# Sheet1.net
KiCad netlist of a schematic drawn in Altium Designer
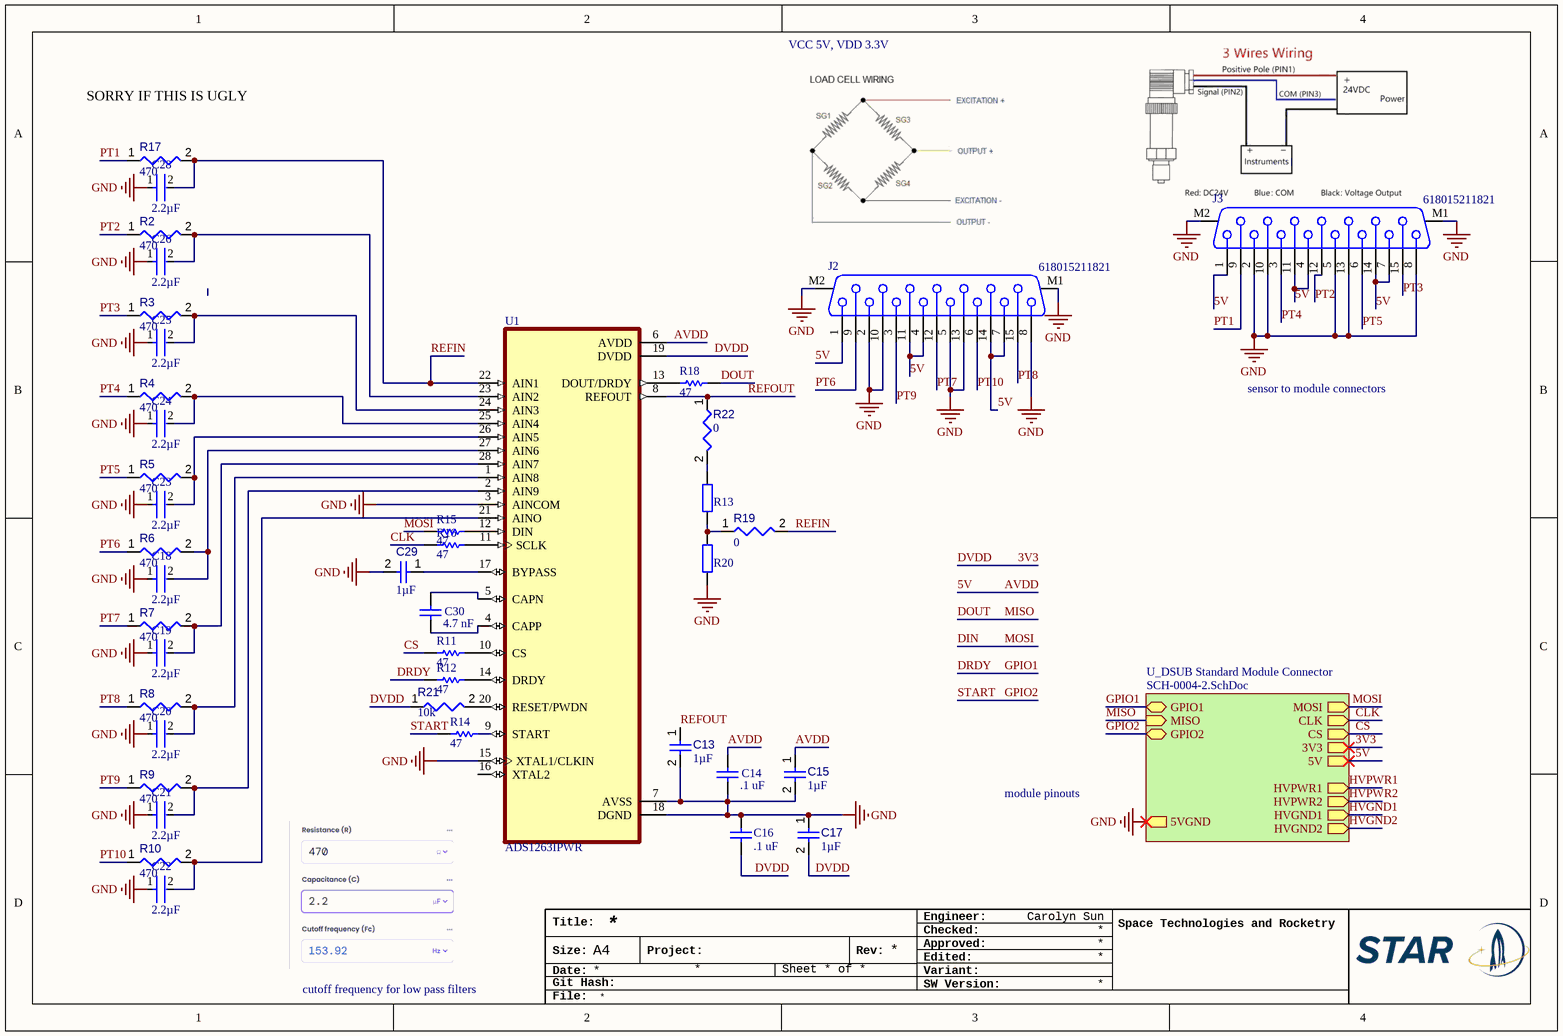
[diagram p0: Sheet1.SchDoc]

(export (version "E")
  (design (tool "Eeschema 10.0.6"))
  (components
    (comp (ref "C13")
      (value "1µF")
      (footprint "CAPC1608X94X35NL15T15")
      (description "Chip Capacitor, 1 uF, +/- 10%, 16 V, 0603 (1608 Metric)")
      (fields (field (name "TOLERANCE") "10%") (field (name "Comment") "Capacitor 1 uF +/- 10% 16 V 0603"))
      (libsource (lib "UCBerkeleySTAR") (part "CAP-NP-2"))
    )
    (comp (ref "C14")
      (value ".1 uF")
      (footprint "CAPC1608X90X35ML10T15")
      (description "Chip Capacitor, 0.1 uF, +/- 10%, 50 V, -55 to 125 degC, 0603 (1608 Metric), RoHS, Tape and Reel")
      (fields (field (name "TOLERANCE") "10%") (field (name "VOLTAGE") "50V"))
      (libsource (lib "Altium Content Vault") (part "CAP-NP-2"))
    )
    (comp (ref "C15")
      (value "1µF")
      (footprint "CAPC1608X94X35NL15T15")
      (description "Chip Capacitor, 1 uF, +/- 10%, 16 V, 0603 (1608 Metric)")
      (fields (field (name "TOLERANCE") "10%") (field (name "Comment") "Capacitor 1 uF +/- 10% 16 V 0603"))
      (libsource (lib "UCBerkeleySTAR") (part "CAP-NP-2"))
    )
    (comp (ref "C16")
      (value ".1 uF")
      (footprint "CAPC1608X90X35ML10T15")
      (description "Chip Capacitor, 0.1 uF, +/- 10%, 50 V, -55 to 125 degC, 0603 (1608 Metric), RoHS, Tape and Reel")
      (fields (field (name "TOLERANCE") "10%") (field (name "VOLTAGE") "50V"))
      (libsource (lib "Altium Content Vault") (part "CAP-NP-2"))
    )
    (comp (ref "C17")
      (value "1µF")
      (footprint "CAPC1608X94X35NL15T15")
      (description "Chip Capacitor, 1 uF, +/- 10%, 16 V, 0603 (1608 Metric)")
      (fields (field (name "TOLERANCE") "10%") (field (name "Comment") "Capacitor 1 uF +/- 10% 16 V 0603"))
      (libsource (lib "UCBerkeleySTAR") (part "CAP-NP-2"))
    )
    (comp (ref "C18")
      (value "2.2µF")
      (footprint "FP-CL21-IPC_B")
      (fields (field (name "Comment") "CL21B225KPFNNNE"))
      (libsource (lib "UCBerkeleySTAR") (part "b4654b650e69147ec39a6b967a45e02"))
    )
    (comp (ref "C19")
      (value "2.2µF")
      (footprint "FP-CL21-IPC_B")
      (fields (field (name "Comment") "CL21B225KPFNNNE"))
      (libsource (lib "UCBerkeleySTAR") (part "b4654b650e69147ec39a6b967a45e02"))
    )
    (comp (ref "C20")
      (value "2.2µF")
      (footprint "FP-CL21-IPC_B")
      (fields (field (name "Comment") "CL21B225KPFNNNE"))
      (libsource (lib "UCBerkeleySTAR") (part "b4654b650e69147ec39a6b967a45e02"))
    )
    (comp (ref "C21")
      (value "2.2µF")
      (footprint "FP-CL21-IPC_B")
      (fields (field (name "Comment") "CL21B225KPFNNNE"))
      (libsource (lib "UCBerkeleySTAR") (part "b4654b650e69147ec39a6b967a45e02"))
    )
    (comp (ref "C22")
      (value "2.2µF")
      (footprint "FP-CL21-IPC_B")
      (fields (field (name "Comment") "CL21B225KPFNNNE"))
      (libsource (lib "UCBerkeleySTAR") (part "b4654b650e69147ec39a6b967a45e02"))
    )
    (comp (ref "C23")
      (value "2.2µF")
      (footprint "FP-CL21-IPC_B")
      (fields (field (name "Comment") "CL21B225KPFNNNE"))
      (libsource (lib "UCBerkeleySTAR") (part "b4654b650e69147ec39a6b967a45e02"))
    )
    (comp (ref "C24")
      (value "2.2µF")
      (footprint "FP-CL21-IPC_B")
      (fields (field (name "Comment") "CL21B225KPFNNNE"))
      (libsource (lib "UCBerkeleySTAR") (part "b4654b650e69147ec39a6b967a45e02"))
    )
    (comp (ref "C25")
      (value "2.2µF")
      (footprint "FP-CL21-IPC_B")
      (fields (field (name "Comment") "CL21B225KPFNNNE"))
      (libsource (lib "UCBerkeleySTAR") (part "b4654b650e69147ec39a6b967a45e02"))
    )
    (comp (ref "C26")
      (value "2.2µF")
      (footprint "FP-CL21-IPC_B")
      (fields (field (name "Comment") "CL21B225KPFNNNE"))
      (libsource (lib "UCBerkeleySTAR") (part "b4654b650e69147ec39a6b967a45e02"))
    )
    (comp (ref "C28")
      (value "2.2µF")
      (footprint "FP-CL21-IPC_B")
      (fields (field (name "Comment") "CL21B225KPFNNNE"))
      (libsource (lib "UCBerkeleySTAR") (part "b4654b650e69147ec39a6b967a45e02"))
    )
    (comp (ref "C29")
      (value "1µF")
      (footprint "CAPC1608X94X35NL15T15")
      (description "Chip Capacitor, 1 uF, +/- 10%, 16 V, 0603 (1608 Metric)")
      (fields (field (name "TOLERANCE") "10%") (field (name "Comment") "Capacitor 1 uF +/- 10% 16 V 0603"))
      (libsource (lib "UCBerkeleySTAR") (part "CAP-NP-2"))
    )
    (comp (ref "C30")
      (value "4.7 nF")
      (footprint "CAPC1608X90X35ML10T15")
      (fields (field (name "PART NUMBER") "GRM188R71H472KA01D") (field (name "MANUFACTURER") "Murata"))
      (libsource (lib "Altium Content Vault") (part "CAP"))
    )
    (comp (ref "J2")
      (value "618015211821")
      (footprint "618015211821")
      (description "D Type Connector, 15 Contact(s), Female, Solder Terminal, Locking, Plug")
      (libsource (lib "UCBerkeleySTAR") (part "D-Sub_Female_15p"))
    )
    (comp (ref "J3")
      (value "618015211821")
      (footprint "618015211821")
      (description "D Type Connector, 15 Contact(s), Female, Solder Terminal, Locking, Plug")
      (libsource (lib "UCBerkeleySTAR") (part "D-Sub_Female_15p"))
    )
    (comp (ref "R2")
      (value "470")
      (footprint "RESC0805(2012)_L")
      (description "470R 0.125W 5% 0805 (2012 Metric)  SMD")
      (fields (field (name "POWER") "125mW") (field (name "TOLERANCE") "5%"))
      (libsource (lib "UCBerkeleySTAR") (part "470R5J"))
    )
    (comp (ref "R3")
      (value "470")
      (footprint "RESC0805(2012)_L")
      (description "470R 0.125W 5% 0805 (2012 Metric)  SMD")
      (fields (field (name "POWER") "125mW") (field (name "TOLERANCE") "5%"))
      (libsource (lib "UCBerkeleySTAR") (part "470R5J"))
    )
    (comp (ref "R4")
      (value "470")
      (footprint "RESC0805(2012)_L")
      (description "470R 0.125W 5% 0805 (2012 Metric)  SMD")
      (fields (field (name "POWER") "125mW") (field (name "TOLERANCE") "5%"))
      (libsource (lib "UCBerkeleySTAR") (part "470R5J"))
    )
    (comp (ref "R5")
      (value "470")
      (footprint "RESC0805(2012)_L")
      (description "470R 0.125W 5% 0805 (2012 Metric)  SMD")
      (fields (field (name "POWER") "125mW") (field (name "TOLERANCE") "5%"))
      (libsource (lib "UCBerkeleySTAR") (part "470R5J"))
    )
    (comp (ref "R6")
      (value "470")
      (footprint "RESC0805(2012)_L")
      (description "470R 0.125W 5% 0805 (2012 Metric)  SMD")
      (fields (field (name "POWER") "125mW") (field (name "TOLERANCE") "5%"))
      (libsource (lib "UCBerkeleySTAR") (part "470R5J"))
    )
    (comp (ref "R7")
      (value "470")
      (footprint "RESC0805(2012)_L")
      (description "470R 0.125W 5% 0805 (2012 Metric)  SMD")
      (fields (field (name "POWER") "125mW") (field (name "TOLERANCE") "5%"))
      (libsource (lib "UCBerkeleySTAR") (part "470R5J"))
    )
    (comp (ref "R8")
      (value "470")
      (footprint "RESC0805(2012)_L")
      (description "470R 0.125W 5% 0805 (2012 Metric)  SMD")
      (fields (field (name "POWER") "125mW") (field (name "TOLERANCE") "5%"))
      (libsource (lib "UCBerkeleySTAR") (part "470R5J"))
    )
    (comp (ref "R9")
      (value "470")
      (footprint "RESC0805(2012)_L")
      (description "470R 0.125W 5% 0805 (2012 Metric)  SMD")
      (fields (field (name "POWER") "125mW") (field (name "TOLERANCE") "5%"))
      (libsource (lib "UCBerkeleySTAR") (part "470R5J"))
    )
    (comp (ref "R10")
      (value "470")
      (footprint "RESC0805(2012)_L")
      (description "470R 0.125W 5% 0805 (2012 Metric)  SMD")
      (fields (field (name "POWER") "125mW") (field (name "TOLERANCE") "5%"))
      (libsource (lib "UCBerkeleySTAR") (part "470R5J"))
    )
    (comp (ref "R11")
      (value "47")
      (footprint "RESC1609X50X30LL10T20")
      (fields (field (name "MANUFACTURER") "Vishay Dale") (field (name "PART NUMBER") "CRCW060347R0FKEA"))
      (libsource (lib "Altium Content Vault") (part "RES"))
    )
    (comp (ref "R12")
      (value "47")
      (footprint "RESC1609X50X30LL10T20")
      (fields (field (name "MANUFACTURER") "Vishay Dale") (field (name "PART NUMBER") "CRCW060347R0FKEA"))
      (libsource (lib "Altium Content Vault") (part "RES"))
    )
    (comp (ref "R13")
      (value "RES_0603")
      (footprint "RES_0603")
      (description "Resistor SMD 0603")
      (fields (field (name "SOURCE") "Schematic-Lib-PhilsLab.SchLib"))
      (libsource (lib "UCBerkeleySTAR") (part "RES_5931"))
    )
    (comp (ref "R14")
      (value "47")
      (footprint "RESC1609X50X30LL10T20")
      (fields (field (name "MANUFACTURER") "Vishay Dale") (field (name "PART NUMBER") "CRCW060347R0FKEA"))
      (libsource (lib "Altium Content Vault") (part "RES"))
    )
    (comp (ref "R15")
      (value "47")
      (footprint "RESC1609X50X30LL10T20")
      (fields (field (name "MANUFACTURER") "Vishay Dale") (field (name "PART NUMBER") "CRCW060347R0FKEA"))
      (libsource (lib "Altium Content Vault") (part "RES"))
    )
    (comp (ref "R16")
      (value "47")
      (footprint "RESC1609X50X30LL10T20")
      (fields (field (name "MANUFACTURER") "Vishay Dale") (field (name "PART NUMBER") "CRCW060347R0FKEA"))
      (libsource (lib "Altium Content Vault") (part "RES"))
    )
    (comp (ref "R17")
      (value "470")
      (footprint "RESC0805(2012)_L")
      (description "470R 0.125W 5% 0805 (2012 Metric)  SMD")
      (fields (field (name "POWER") "125mW") (field (name "TOLERANCE") "5%"))
      (libsource (lib "UCBerkeleySTAR") (part "470R5J"))
    )
    (comp (ref "R18")
      (value "47")
      (footprint "RESC1609X50X30LL10T20")
      (fields (field (name "MANUFACTURER") "Vishay Dale") (field (name "PART NUMBER") "CRCW060347R0FKEA"))
      (libsource (lib "Altium Content Vault") (part "RES"))
    )
    (comp (ref "R19")
      (value "0")
      (footprint "RESC0603(1608)_L")
      (description "Jumper 0603")
      (libsource (lib "UCBerkeleySTAR") (part "RES-2"))
    )
    (comp (ref "R20")
      (value "RES_0603")
      (footprint "RES_0603")
      (description "Resistor SMD 0603")
      (fields (field (name "SOURCE") "Schematic-Lib-PhilsLab.SchLib"))
      (libsource (lib "UCBerkeleySTAR") (part "RES_5931"))
    )
    (comp (ref "R21")
      (value "10k")
      (footprint "RESC1608X55X25ML10T15")
      (description "Chip Resistor, 10 KOhm, +/- 1%, 01 W, -55 to 155 degC, 0603 (1608 Metric)")
      (fields (field (name "POWER") "100mW") (field (name "TOLERANCE") "1%"))
      (libsource (lib "UCBerkeleySTAR") (part "RES-2"))
    )
    (comp (ref "R22")
      (value "0")
      (footprint "RESC0603(1608)_L")
      (description "Jumper 0603")
      (libsource (lib "UCBerkeleySTAR") (part "RES-2"))
    )
    (comp (ref "U1")
      (value "ADS1263IPWR")
      (footprint "SOP65P640X120-28N")
      (description "32-bit 38-kSPS 10-ch delta-sigma ADC with PGA, VREF and auxiliary ADC for factory automation")
      (fields (field (name "MF") "Texas Instruments"))
      (libsource (lib "UCBerkeleySTAR") (part "ADS1263IPWR"))
    )
  )
  (nets
    (net (code "1") (name "/3V3") (class "Default")
      (node (ref "C16") (pin "1") (pinfunction "1_1") (pintype "passive"))
      (node (ref "C17") (pin "2") (pinfunction "2_2") (pintype "passive"))
      (node (ref "R21") (pin "1") (pinfunction "1_1") (pintype "passive"))
      (node (ref "U1") (pin "19") (pinfunction "DVDD_19") (pintype "power_in"))
    )
    (net (code "2") (name "/5V") (class "Default")
      (node (ref "C14") (pin "2") (pinfunction "2_2") (pintype "passive"))
      (node (ref "C15") (pin "1") (pinfunction "1_1") (pintype "passive"))
      (node (ref "J2") (pin "1") (pinfunction "1_1") (pintype "passive"))
      (node (ref "J2") (pin "11") (pinfunction "11_11") (pintype "passive"))
      (node (ref "J2") (pin "14") (pinfunction "14_14") (pintype "passive"))
      (node (ref "J2") (pin "4") (pinfunction "4_4") (pintype "passive"))
      (node (ref "J2") (pin "7") (pinfunction "7_7") (pintype "passive"))
      (node (ref "J3") (pin "1") (pinfunction "1_1") (pintype "passive"))
      (node (ref "J3") (pin "11") (pinfunction "11_11") (pintype "passive"))
      (node (ref "J3") (pin "14") (pinfunction "14_14") (pintype "passive"))
      (node (ref "J3") (pin "4") (pinfunction "4_4") (pintype "passive"))
      (node (ref "J3") (pin "7") (pinfunction "7_7") (pintype "passive"))
      (node (ref "U1") (pin "6") (pinfunction "AVDD_6") (pintype "power_in"))
    )
    (net (code "3") (name "/CLK") (class "Default")
      (node (ref "R16") (pin "1") (pinfunction "1_1") (pintype "passive"))
    )
    (net (code "4") (name "/CS") (class "Default")
      (node (ref "R11") (pin "1") (pinfunction "1_1") (pintype "passive"))
    )
    (net (code "5") (name "/DIN") (class "Default")
      (node (ref "R15") (pin "1") (pinfunction "1_1") (pintype "passive"))
    )
    (net (code "6") (name "/DOUT") (class "Default")
      (node (ref "R18") (pin "2") (pinfunction "2_2") (pintype "passive"))
    )
    (net (code "7") (name "/DRDY") (class "Default")
      (node (ref "R12") (pin "1") (pinfunction "1_1") (pintype "passive"))
    )
    (net (code "8") (name "/GPIO2") (class "Default")
      (node (ref "R14") (pin "1") (pinfunction "1_1") (pintype "passive"))
    )
    (net (code "13") (name "/PT1") (class "Default")
      (node (ref "J3") (pin "9") (pinfunction "9_9") (pintype "passive"))
      (node (ref "R17") (pin "1") (pinfunction "1_1") (pintype "passive"))
    )
    (net (code "14") (name "/PT2") (class "Default")
      (node (ref "J3") (pin "12") (pinfunction "12_12") (pintype "passive"))
      (node (ref "R2") (pin "1") (pinfunction "1_1") (pintype "passive"))
    )
    (net (code "15") (name "/PT3") (class "Default")
      (node (ref "J3") (pin "15") (pinfunction "15_15") (pintype "passive"))
      (node (ref "R3") (pin "1") (pinfunction "1_1") (pintype "passive"))
    )
    (net (code "16") (name "/PT4") (class "Default")
      (node (ref "J3") (pin "3") (pinfunction "3_3") (pintype "passive"))
      (node (ref "R4") (pin "1") (pinfunction "1_1") (pintype "passive"))
    )
    (net (code "17") (name "/PT5") (class "Default")
      (node (ref "J3") (pin "6") (pinfunction "6_6") (pintype "passive"))
      (node (ref "R5") (pin "1") (pinfunction "1_1") (pintype "passive"))
    )
    (net (code "18") (name "/PT6") (class "Default")
      (node (ref "J2") (pin "9") (pinfunction "9_9") (pintype "passive"))
      (node (ref "R6") (pin "1") (pinfunction "1_1") (pintype "passive"))
    )
    (net (code "19") (name "/PT7") (class "Default")
      (node (ref "J2") (pin "12") (pinfunction "12_12") (pintype "passive"))
      (node (ref "R7") (pin "1") (pinfunction "1_1") (pintype "passive"))
    )
    (net (code "20") (name "/PT8") (class "Default")
      (node (ref "J2") (pin "15") (pinfunction "15_15") (pintype "passive"))
      (node (ref "R8") (pin "1") (pinfunction "1_1") (pintype "passive"))
    )
    (net (code "21") (name "/PT9") (class "Default")
      (node (ref "J2") (pin "3") (pinfunction "3_3") (pintype "passive"))
      (node (ref "R9") (pin "1") (pinfunction "1_1") (pintype "passive"))
    )
    (net (code "22") (name "/PT10") (class "Default")
      (node (ref "J2") (pin "6") (pinfunction "6_6") (pintype "passive"))
      (node (ref "R10") (pin "1") (pinfunction "1_1") (pintype "passive"))
    )
    (net (code "23") (name "/REFIN") (class "Default")
      (node (ref "C28") (pin "2") (pinfunction "2_2") (pintype "passive"))
      (node (ref "R17") (pin "2") (pinfunction "2_2") (pintype "passive"))
      (node (ref "R19") (pin "2") (pinfunction "2_2") (pintype "passive"))
      (node (ref "U1") (pin "22") (pinfunction "AIN1_22") (pintype "input"))
    )
    (net (code "24") (name "/REFOUT") (class "Default")
      (node (ref "C13") (pin "1") (pinfunction "1_1") (pintype "passive"))
      (node (ref "R22") (pin "1") (pinfunction "1_1") (pintype "passive"))
      (node (ref "U1") (pin "8") (pinfunction "REFOUT_8") (pintype "output"))
    )
    (net (code "25") (name "GND") (class "Default")
      (node (ref "C13") (pin "2") (pinfunction "2_2") (pintype "passive"))
      (node (ref "C14") (pin "1") (pinfunction "1_1") (pintype "passive"))
      (node (ref "C15") (pin "2") (pinfunction "2_2") (pintype "passive"))
      (node (ref "C16") (pin "2") (pinfunction "2_2") (pintype "passive"))
      (node (ref "C17") (pin "1") (pinfunction "1_1") (pintype "passive"))
      (node (ref "C18") (pin "1") (pinfunction "1_1") (pintype "passive"))
      (node (ref "C19") (pin "1") (pinfunction "1_1") (pintype "passive"))
      (node (ref "C20") (pin "1") (pinfunction "1_1") (pintype "passive"))
      (node (ref "C21") (pin "1") (pinfunction "1_1") (pintype "passive"))
      (node (ref "C22") (pin "1") (pinfunction "1_1") (pintype "passive"))
      (node (ref "C23") (pin "1") (pinfunction "1_1") (pintype "passive"))
      (node (ref "C24") (pin "1") (pinfunction "1_1") (pintype "passive"))
      (node (ref "C25") (pin "1") (pinfunction "1_1") (pintype "passive"))
      (node (ref "C26") (pin "1") (pinfunction "1_1") (pintype "passive"))
      (node (ref "C28") (pin "1") (pinfunction "1_1") (pintype "passive"))
      (node (ref "C29") (pin "2") (pinfunction "2_2") (pintype "passive"))
      (node (ref "J2") (pin "10") (pinfunction "10_10") (pintype "passive"))
      (node (ref "J2") (pin "13") (pinfunction "13_13") (pintype "passive"))
      (node (ref "J2") (pin "2") (pinfunction "2_2") (pintype "passive"))
      (node (ref "J2") (pin "5") (pinfunction "5_5") (pintype "passive"))
      (node (ref "J2") (pin "8") (pinfunction "8_8") (pintype "passive"))
      (node (ref "J2") (pin "M1") (pinfunction "M1_M1") (pintype "passive"))
      (node (ref "J2") (pin "M2") (pinfunction "M2_M2") (pintype "passive"))
      (node (ref "J3") (pin "10") (pinfunction "10_10") (pintype "passive"))
      (node (ref "J3") (pin "13") (pinfunction "13_13") (pintype "passive"))
      (node (ref "J3") (pin "2") (pinfunction "2_2") (pintype "passive"))
      (node (ref "J3") (pin "5") (pinfunction "5_5") (pintype "passive"))
      (node (ref "J3") (pin "8") (pinfunction "8_8") (pintype "passive"))
      (node (ref "J3") (pin "M1") (pinfunction "M1_M1") (pintype "passive"))
      (node (ref "J3") (pin "M2") (pinfunction "M2_M2") (pintype "passive"))
      (node (ref "R20") (pin "2") (pinfunction "2_2") (pintype "passive"))
      (node (ref "U1") (pin "15") (pinfunction "XTAL1/CLKIN_15") (pintype "bidirectional"))
      (node (ref "U1") (pin "18") (pinfunction "DGND_18") (pintype "power_in"))
      (node (ref "U1") (pin "3") (pinfunction "AINCOM_3") (pintype "input"))
      (node (ref "U1") (pin "7") (pinfunction "AVSS_7") (pintype "power_in"))
    )
    (net (code "26") (name "Net-(R13-Pad1)") (class "Default")
      (node (ref "R13") (pin "1") (pinfunction "1_1") (pintype "passive"))
      (node (ref "R22") (pin "2") (pinfunction "2_2") (pintype "passive"))
    )
    (net (code "27") (name "Net-(R13-Pad2)") (class "Default")
      (node (ref "R13") (pin "2") (pinfunction "2_2") (pintype "passive"))
      (node (ref "R19") (pin "1") (pinfunction "1_1") (pintype "passive"))
      (node (ref "R20") (pin "1") (pinfunction "1_1") (pintype "passive"))
    )
    (net (code "28") (name "Net-(U1-AIN2)") (class "Default")
      (node (ref "C26") (pin "2") (pinfunction "2_2") (pintype "passive"))
      (node (ref "R2") (pin "2") (pinfunction "2_2") (pintype "passive"))
      (node (ref "U1") (pin "23") (pinfunction "AIN2_23") (pintype "input"))
    )
    (net (code "29") (name "Net-(U1-AIN3)") (class "Default")
      (node (ref "C25") (pin "2") (pinfunction "2_2") (pintype "passive"))
      (node (ref "R3") (pin "2") (pinfunction "2_2") (pintype "passive"))
      (node (ref "U1") (pin "24") (pinfunction "AIN3_24") (pintype "input"))
    )
    (net (code "30") (name "Net-(U1-AIN4)") (class "Default")
      (node (ref "C24") (pin "2") (pinfunction "2_2") (pintype "passive"))
      (node (ref "R4") (pin "2") (pinfunction "2_2") (pintype "passive"))
      (node (ref "U1") (pin "25") (pinfunction "AIN4_25") (pintype "input"))
    )
    (net (code "31") (name "Net-(U1-AIN5)") (class "Default")
      (node (ref "C23") (pin "2") (pinfunction "2_2") (pintype "passive"))
      (node (ref "R5") (pin "2") (pinfunction "2_2") (pintype "passive"))
      (node (ref "U1") (pin "26") (pinfunction "AIN5_26") (pintype "input"))
    )
    (net (code "32") (name "Net-(U1-AIN6)") (class "Default")
      (node (ref "C18") (pin "2") (pinfunction "2_2") (pintype "passive"))
      (node (ref "R6") (pin "2") (pinfunction "2_2") (pintype "passive"))
      (node (ref "U1") (pin "27") (pinfunction "AIN6_27") (pintype "input"))
    )
    (net (code "33") (name "Net-(U1-AIN7)") (class "Default")
      (node (ref "C19") (pin "2") (pinfunction "2_2") (pintype "passive"))
      (node (ref "R7") (pin "2") (pinfunction "2_2") (pintype "passive"))
      (node (ref "U1") (pin "28") (pinfunction "AIN7_28") (pintype "input"))
    )
    (net (code "34") (name "Net-(U1-AIN8)") (class "Default")
      (node (ref "C20") (pin "2") (pinfunction "2_2") (pintype "passive"))
      (node (ref "R8") (pin "2") (pinfunction "2_2") (pintype "passive"))
      (node (ref "U1") (pin "1") (pinfunction "AIN8_1") (pintype "input"))
    )
    (net (code "35") (name "Net-(U1-AIN9)") (class "Default")
      (node (ref "C21") (pin "2") (pinfunction "2_2") (pintype "passive"))
      (node (ref "R9") (pin "2") (pinfunction "2_2") (pintype "passive"))
      (node (ref "U1") (pin "2") (pinfunction "AIN9_2") (pintype "input"))
    )
    (net (code "36") (name "Net-(U1-AINO)") (class "Default")
      (node (ref "C22") (pin "2") (pinfunction "2_2") (pintype "passive"))
      (node (ref "R10") (pin "2") (pinfunction "2_2") (pintype "passive"))
      (node (ref "U1") (pin "21") (pinfunction "AINO_21") (pintype "input"))
    )
    (net (code "37") (name "Net-(U1-BYPASS)") (class "Default")
      (node (ref "C29") (pin "1") (pinfunction "1_1") (pintype "passive"))
      (node (ref "U1") (pin "17") (pinfunction "BYPASS_17") (pintype "bidirectional"))
    )
    (net (code "38") (name "Net-(U1-CAPN)") (class "Default")
      (node (ref "C30") (pin "2") (pinfunction "2_2") (pintype "passive"))
      (node (ref "U1") (pin "5") (pinfunction "CAPN_5") (pintype "bidirectional"))
    )
    (net (code "39") (name "Net-(U1-CAPP)") (class "Default")
      (node (ref "C30") (pin "1") (pinfunction "1_1") (pintype "passive"))
      (node (ref "U1") (pin "4") (pinfunction "CAPP_4") (pintype "bidirectional"))
    )
    (net (code "40") (name "Net-(U1-CS)") (class "Default")
      (node (ref "R11") (pin "2") (pinfunction "2_2") (pintype "passive"))
      (node (ref "U1") (pin "10") (pinfunction "CS_10") (pintype "bidirectional"))
    )
    (net (code "41") (name "Net-(U1-DIN)") (class "Default")
      (node (ref "R15") (pin "2") (pinfunction "2_2") (pintype "passive"))
      (node (ref "U1") (pin "12") (pinfunction "DIN_12") (pintype "input"))
    )
    (net (code "42") (name "Net-(U1-DOUT{slash}DRDY)") (class "Default")
      (node (ref "R18") (pin "1") (pinfunction "1_1") (pintype "passive"))
      (node (ref "U1") (pin "13") (pinfunction "DOUT/DRDY_13") (pintype "output"))
    )
    (net (code "43") (name "Net-(U1-DRDY)") (class "Default")
      (node (ref "R12") (pin "2") (pinfunction "2_2") (pintype "passive"))
      (node (ref "U1") (pin "14") (pinfunction "DRDY_14") (pintype "bidirectional"))
    )
    (net (code "44") (name "Net-(U1-RESET{slash}PWDN)") (class "Default")
      (node (ref "R21") (pin "2") (pinfunction "2_2") (pintype "passive"))
      (node (ref "U1") (pin "20") (pinfunction "RESET/PWDN_20") (pintype "bidirectional"))
    )
    (net (code "45") (name "Net-(U1-SCLK)") (class "Default")
      (node (ref "R16") (pin "2") (pinfunction "2_2") (pintype "passive"))
      (node (ref "U1") (pin "11") (pinfunction "SCLK_11") (pintype "input"))
    )
    (net (code "46") (name "Net-(U1-START)") (class "Default")
      (node (ref "R14") (pin "2") (pinfunction "2_2") (pintype "passive"))
      (node (ref "U1") (pin "9") (pinfunction "START_9") (pintype "bidirectional"))
    )
    (net (code "47") (name "unconnected-(U1-XTAL2-Pad16)") (class "Default")
      (node (ref "U1") (pin "16") (pinfunction "XTAL2_16") (pintype "bidirectional"))
    )
  )
)
